# SHDN-CURRENT-S04-V00-PSU-3V3.net
KiCad netlist of a schematic drawn in Altium Designer
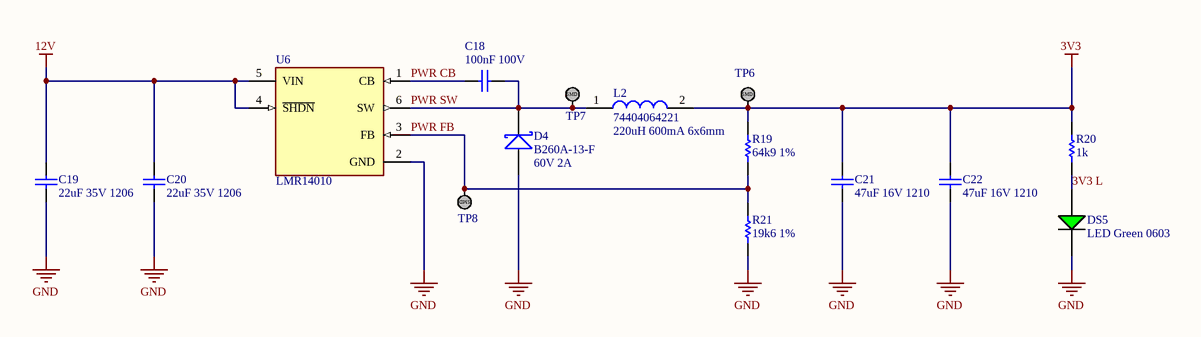
[diagram p0: SHDN-CURRENT-S04-V00-PSU-3V3.SchDoc]

(export (version "E")
  (design (tool "Eeschema 10.0.6"))
  (components
    (comp (ref "C18")
      (value "100nF 100V")
      (footprint "Cap_Ceramic_0603")
      (description "Capacitor, Ceramic, SMD, 100nF, 100V, 5%, X7R, 0603")
      (libsource (lib "StandardCapacitors") (part "100nF 100V 5% X7R 0603"))
    )
    (comp (ref "C19")
      (value "22uF 35V 1206")
      (footprint "Cap_Ceramic_1206")
      (description "Capacitor, Ceramic, SMD, 22uF, 35V, 10%, X7R, 1206")
      (libsource (lib "StandardCapacitors") (part "22uF 35V 10% X7R 1206"))
    )
    (comp (ref "C20")
      (value "22uF 35V 1206")
      (footprint "Cap_Ceramic_1206")
      (description "Capacitor, Ceramic, SMD, 22uF, 35V, 10%, X7R, 1206")
      (libsource (lib "StandardCapacitors") (part "22uF 35V 10% X7R 1206"))
    )
    (comp (ref "C21")
      (value "47uF 16V 1210")
      (footprint "Cap_Ceramic_1210")
      (description "Capacitor, Ceramic, SMD, 47uF, 16V, 5%, X7R, 1210")
      (libsource (lib "StandardCapacitors") (part "47uF 16V 10% X7R 1210"))
    )
    (comp (ref "C22")
      (value "47uF 16V 1210")
      (footprint "Cap_Ceramic_1210")
      (description "Capacitor, Ceramic, SMD, 47uF, 16V, 5%, X7R, 1210")
      (libsource (lib "StandardCapacitors") (part "47uF 16V 10% X7R 1210"))
    )
    (comp (ref "D4")
      (value "B260A-13-F")
      (footprint "SMA")
      (description "Diode, Schottky Barrier Rectifier, 60 V, 2 A, B260A-13-F")
      (libsource (lib "QUTMS_DiodeLibrary") (part "B260A-13-F"))
    )
    (comp (ref "DS5")
      (value "LED Green 0603")
      (footprint "LED GREEN 0603")
      (libsource (lib "QUTMS_LEDLibrary") (part "LED Green 0603"))
    )
    (comp (ref "L2")
      (value "74404064221")
      (footprint "Inductor_6x6mm")
      (description "FIXED IND 220UH 660MA 850 MOHM")
      (libsource (lib "QUTMS_InductorLibrary") (part "74404064221"))
    )
    (comp (ref "R19")
      (value "64k9 1%")
      (footprint "Res_ThinFilm_0603")
      (description "Resistor, SMD, 64k9, 0.1W, 5%, 0603")
      (libsource (lib "StandardResistors") (part "64k9 1% 0603"))
    )
    (comp (ref "R20")
      (value "1k")
      (footprint "Res_ThinFilm_0603")
      (description "Resistor, SMD, 1k, 0.1W, 5%, 0603")
      (libsource (lib "StandardResistors") (part "1k 5% 0603"))
    )
    (comp (ref "R21")
      (value "19k6 1%")
      (footprint "Res_ThinFilm_0603")
      (description "Resistor, SMD, 19k6, 0.1W, 5%, 0603")
      (libsource (lib "StandardResistors") (part "19k6 1% 0603"))
    )
    (comp (ref "TP6")
      (value "TestPoint_SMD")
      (footprint "TestPointSMD")
      (libsource (lib "StandardTest") (part "TestPoint_SMD"))
    )
    (comp (ref "TP7")
      (value "TestPoint_SMD")
      (footprint "TestPointSMD")
      (libsource (lib "StandardTest") (part "TestPoint_SMD"))
    )
    (comp (ref "TP8")
      (value "TestPoint_SMD")
      (footprint "TestPointSMD")
      (libsource (lib "StandardTest") (part "TestPoint_SMD"))
    )
    (comp (ref "U6")
      (value "LMR14010")
      (footprint "LMR14010")
      (libsource (lib "QUTMS_PowerSupplyLibrary") (part "LMR14010"))
    )
  )
  (nets
    (net (code "1") (name "/3V3 L") (class "Default")
      (node (ref "DS5") (pin "1") (pinfunction "A_1") (pintype "passive"))
      (node (ref "R20") (pin "1") (pinfunction "1_1") (pintype "passive"))
    )
    (net (code "2") (name "/PWR CB") (class "Default")
      (node (ref "C18") (pin "1") (pinfunction "1_1") (pintype "passive"))
      (node (ref "U6") (pin "1") (pinfunction "CB_1") (pintype "input"))
    )
    (net (code "3") (name "/PWR FB") (class "Default")
      (node (ref "R19") (pin "1") (pinfunction "1_1") (pintype "passive"))
      (node (ref "R21") (pin "2") (pinfunction "2_2") (pintype "passive"))
      (node (ref "TP8") (pin "1") (pinfunction "1_1") (pintype "passive"))
      (node (ref "U6") (pin "3") (pinfunction "FB_3") (pintype "input"))
    )
    (net (code "4") (name "/PWR SW") (class "Default")
      (node (ref "C18") (pin "2") (pinfunction "2_2") (pintype "passive"))
      (node (ref "D4") (pin "K") (pinfunction "K_K") (pintype "passive"))
      (node (ref "L2") (pin "1") (pinfunction "1_1") (pintype "passive"))
      (node (ref "TP7") (pin "1") (pinfunction "1_1") (pintype "passive"))
      (node (ref "U6") (pin "6") (pinfunction "SW_6") (pintype "output"))
    )
    (net (code "5") (name "3V3") (class "Default")
      (node (ref "C21") (pin "2") (pinfunction "2_2") (pintype "passive"))
      (node (ref "C22") (pin "2") (pinfunction "2_2") (pintype "passive"))
      (node (ref "L2") (pin "2") (pinfunction "2_2") (pintype "passive"))
      (node (ref "R19") (pin "2") (pinfunction "2_2") (pintype "passive"))
      (node (ref "R20") (pin "2") (pinfunction "2_2") (pintype "passive"))
      (node (ref "TP6") (pin "1") (pinfunction "1_1") (pintype "passive"))
    )
    (net (code "6") (name "12V") (class "Default")
      (node (ref "C19") (pin "2") (pinfunction "2_2") (pintype "passive"))
      (node (ref "C20") (pin "2") (pinfunction "2_2") (pintype "passive"))
      (node (ref "U6") (pin "4") (pinfunction "~{SHDN}_4") (pintype "input"))
      (node (ref "U6") (pin "5") (pinfunction "VIN_5") (pintype "power_in"))
    )
    (net (code "7") (name "GND") (class "Default")
      (node (ref "C19") (pin "1") (pinfunction "1_1") (pintype "passive"))
      (node (ref "C20") (pin "1") (pinfunction "1_1") (pintype "passive"))
      (node (ref "C21") (pin "1") (pinfunction "1_1") (pintype "passive"))
      (node (ref "C22") (pin "1") (pinfunction "1_1") (pintype "passive"))
      (node (ref "D4") (pin "A") (pinfunction "A_A") (pintype "passive"))
      (node (ref "DS5") (pin "2") (pinfunction "C_2") (pintype "passive"))
      (node (ref "R21") (pin "1") (pinfunction "1_1") (pintype "passive"))
      (node (ref "U6") (pin "2") (pinfunction "GND_2") (pintype "power_in"))
    )
  )
)
